# Brduino-MCU1.net
KiCad netlist of a schematic drawn in Altium Designer
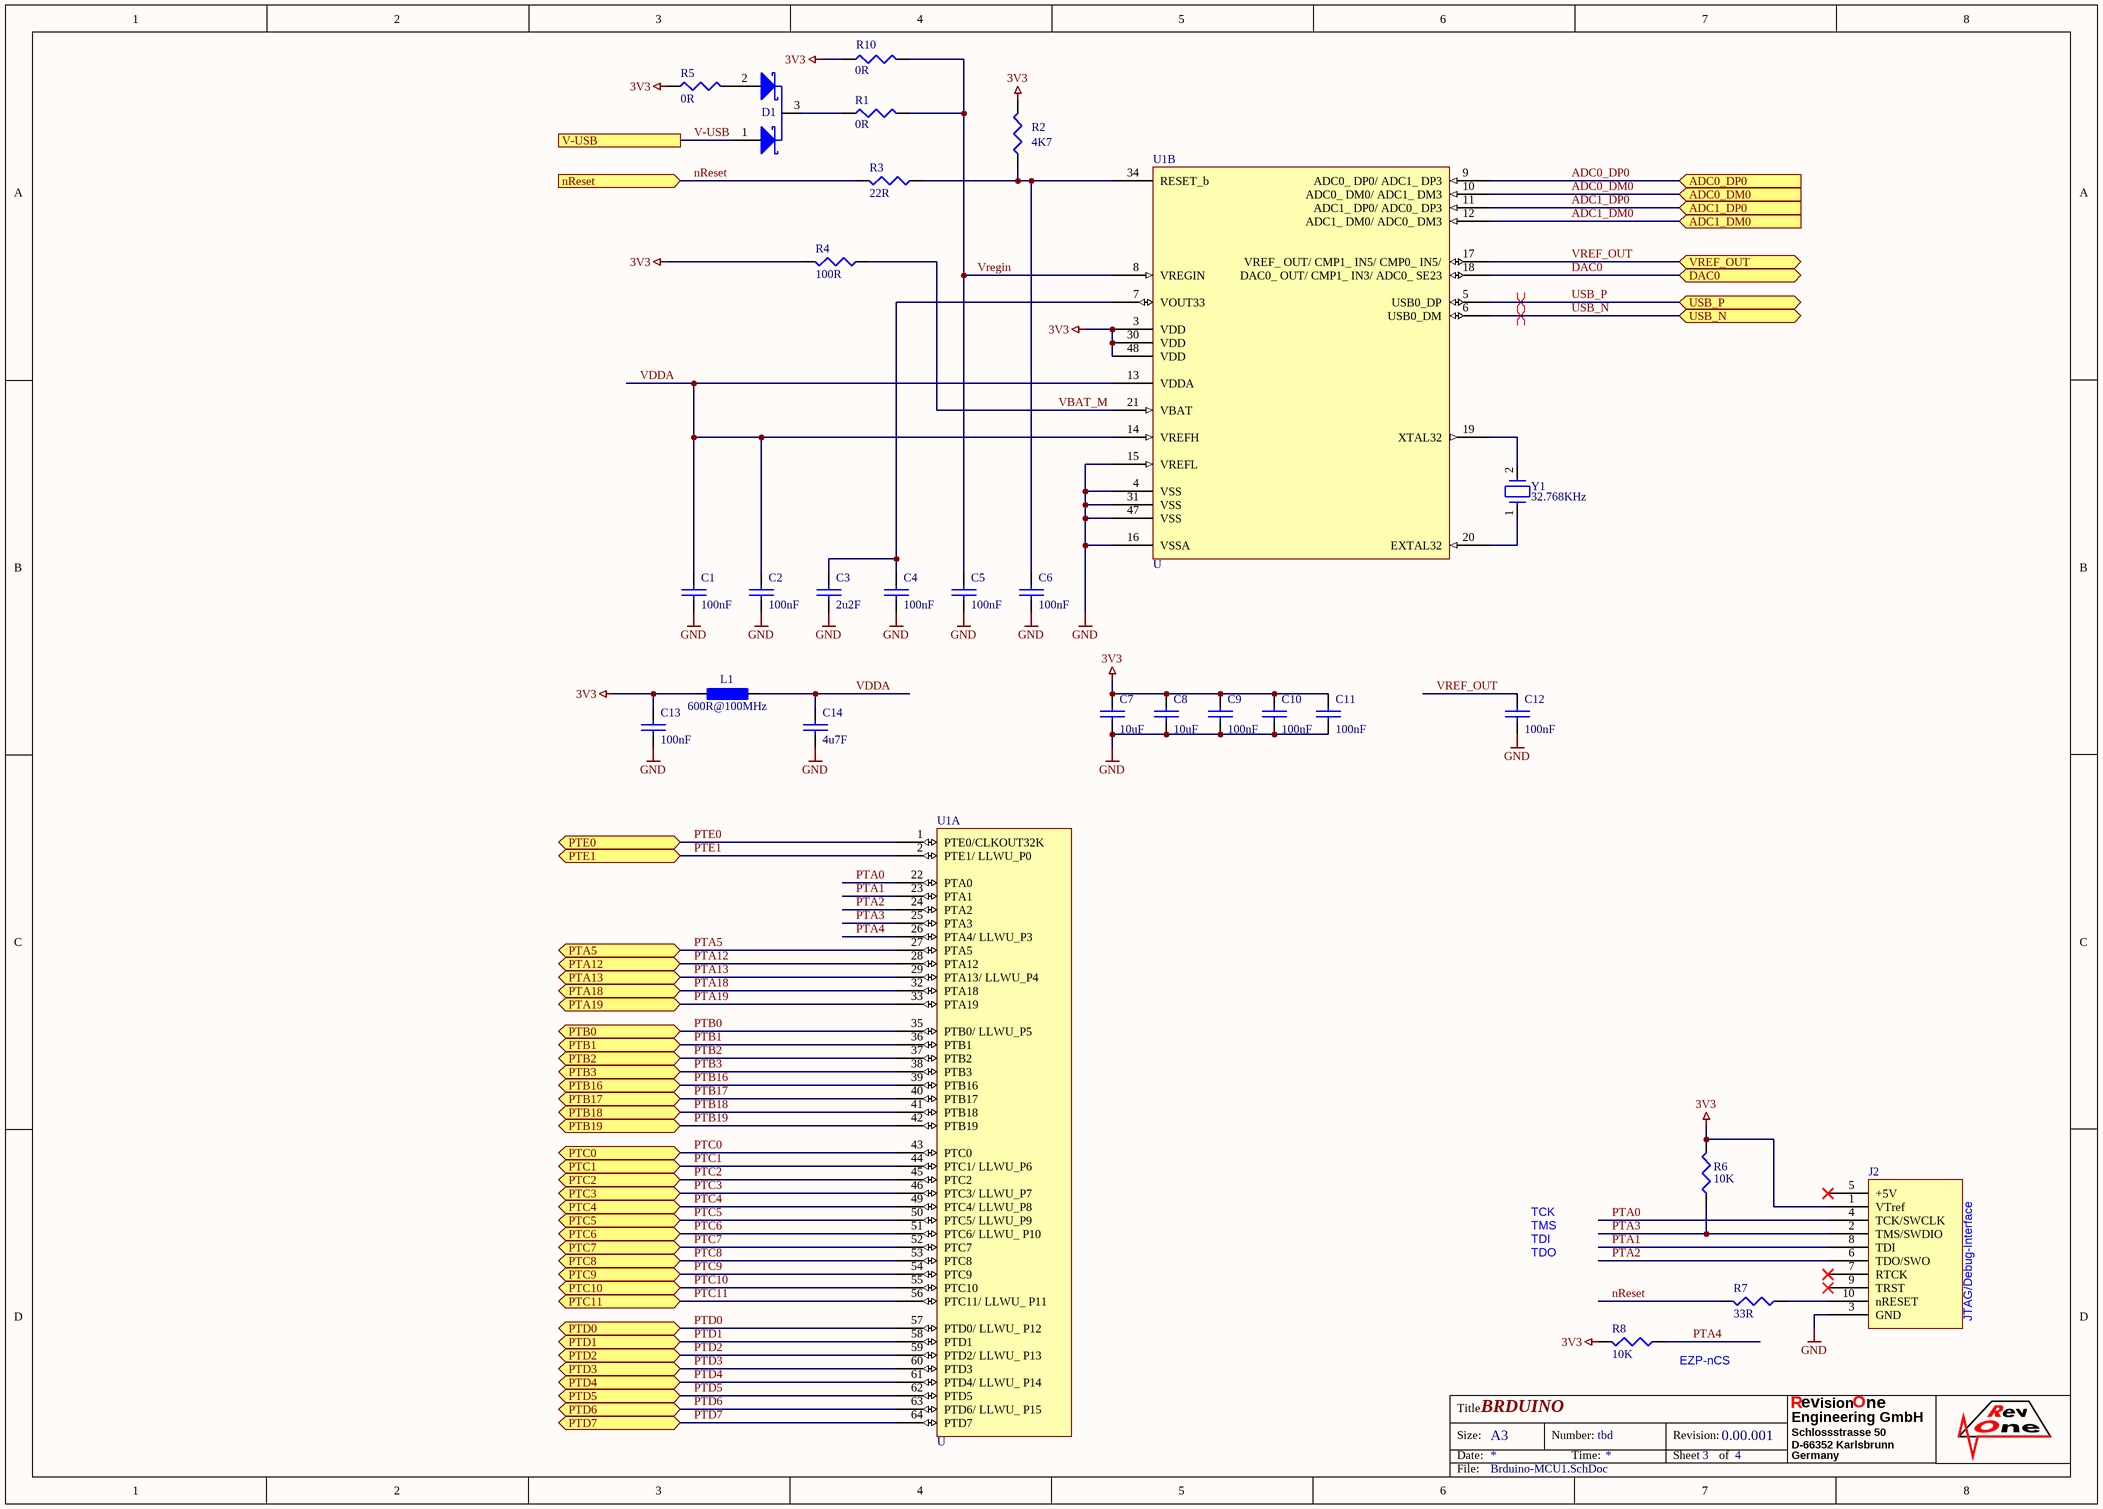
[diagram p0: Brduino-MCU1.SchDoc]

(export (version "E")
  (design (tool "Eeschema 10.0.6"))
  (components
    (comp (ref "C1")
      (value "100nF")
      (footprint "C0402")
      (description "CAP CER 0.1UF 25V X7R 0402")
      (fields (field (name "Comment") "C"))
      (libsource (lib "Brduino-Nano") (part "CAP"))
    )
    (comp (ref "C2")
      (value "100nF")
      (footprint "C0402")
      (description "CAP CER 0.1UF 25V X7R 0402")
      (fields (field (name "Comment") "C"))
      (libsource (lib "Brduino-Nano") (part "CAP"))
    )
    (comp (ref "C3")
      (value "2u2F")
      (footprint "C0603")
      (description "CAP CER 2.2UF 10V X5R 0603")
      (fields (field (name "Comment") "C"))
      (libsource (lib "Brduino-Nano") (part "CAP"))
    )
    (comp (ref "C4")
      (value "100nF")
      (footprint "C0402")
      (description "CAP CER 0.1UF 25V X7R 0402")
      (fields (field (name "Comment") "C"))
      (libsource (lib "Brduino-Nano") (part "CAP"))
    )
    (comp (ref "C5")
      (value "100nF")
      (footprint "C0402")
      (description "CAP CER 0.1UF 25V X7R 0402")
      (fields (field (name "Comment") "C"))
      (libsource (lib "Brduino-Nano") (part "CAP"))
    )
    (comp (ref "C6")
      (value "100nF")
      (footprint "C0402")
      (description "CAP CER 0.1UF 25V X7R 0402")
      (fields (field (name "Comment") "C"))
      (libsource (lib "Brduino-Nano") (part "CAP"))
    )
    (comp (ref "C7")
      (value "10uF")
      (footprint "C0805")
      (description "CAP CER 10UF 10V X7R 0805")
      (fields (field (name "Comment") "C"))
      (libsource (lib "Brduino-Nano") (part "CAP"))
    )
    (comp (ref "C8")
      (value "10uF")
      (footprint "C0805")
      (description "CAP CER 10UF 10V X7R 0805")
      (fields (field (name "Comment") "C"))
      (libsource (lib "Brduino-Nano") (part "CAP"))
    )
    (comp (ref "C9")
      (value "100nF")
      (footprint "C0402")
      (description "CAP CER 0.1UF 25V X7R 0402")
      (fields (field (name "Comment") "C"))
      (libsource (lib "Brduino-Nano") (part "CAP"))
    )
    (comp (ref "C10")
      (value "100nF")
      (footprint "C0402")
      (description "CAP CER 0.1UF 25V X7R 0402")
      (fields (field (name "Comment") "C"))
      (libsource (lib "Brduino-Nano") (part "CAP"))
    )
    (comp (ref "C11")
      (value "100nF")
      (footprint "C0402")
      (description "CAP CER 0.1UF 25V X7R 0402")
      (fields (field (name "Comment") "C"))
      (libsource (lib "Brduino-Nano") (part "CAP"))
    )
    (comp (ref "C12")
      (value "100nF")
      (footprint "C0402")
      (description "CAP CER 0.1UF 25V X7R 0402")
      (fields (field (name "Comment") "C"))
      (libsource (lib "Brduino-Nano") (part "CAP"))
    )
    (comp (ref "C13")
      (value "100nF")
      (footprint "C0402")
      (description "CAP CER 0.1UF 25V X7R 0402")
      (fields (field (name "Comment") "C"))
      (libsource (lib "Brduino-Nano") (part "CAP"))
    )
    (comp (ref "C14")
      (value "4u7F")
      (footprint "C0805")
      (description "CAP CER 4.7UF 10V X7R 0805")
      (fields (field (name "Comment") "C"))
      (libsource (lib "Brduino-Nano") (part "CAP"))
    )
    (comp (ref "D1")
      (value "D")
      (footprint "SOT23")
      (description "DIODE ARRAY SCHOTTKY 30V SOT23-3")
      (libsource (lib "Brduino-Nano") (part "DUALSDIODE-CC"))
    )
    (comp (ref "J2")
      (value "X")
      (footprint "JLINK-NEEDLE")
      (libsource (lib "Brduino-Nano") (part "JLINK-NEEDLE"))
    )
    (comp (ref "L1")
      (value "600R@100MHz")
      (footprint "L0805")
      (description "FERRITE BEAD 600 OHM 0805 1LN")
      (fields (field (name "Comment") "L"))
      (libsource (lib "Brduino-Nano") (part "FERRITE"))
    )
    (comp (ref "R1")
      (value "0R")
      (footprint "R0402")
      (description "RES SMD 0 OHM JUMPER 1/16W 0402")
      (fields (field (name "Comment") "R"))
      (libsource (lib "Brduino-Nano") (part "RES1A"))
    )
    (comp (ref "R2")
      (value "4K7")
      (footprint "R0402")
      (description "RES SMD 4.7K OHM 1% 1/16W 0402")
      (fields (field (name "Comment") "R"))
      (libsource (lib "Brduino-Nano") (part "RES1A"))
    )
    (comp (ref "R3")
      (value "22R")
      (footprint "R0402")
      (description "RES SMD 22 OHM 1% 1/16W 0402")
      (fields (field (name "Comment") "R"))
      (libsource (lib "Brduino-Nano") (part "RES1A"))
    )
    (comp (ref "R4")
      (value "100R")
      (footprint "R0402")
      (description "RES SMD 100 OHM 1% 1/16W 0402")
      (fields (field (name "Comment") "R"))
      (libsource (lib "Brduino-Nano") (part "RES1A"))
    )
    (comp (ref "R5")
      (value "0R")
      (footprint "R0402")
      (description "RES SMD 0 OHM JUMPER 1/16W 0402")
      (fields (field (name "Comment") "R"))
      (libsource (lib "Brduino-Nano") (part "RES1A"))
    )
    (comp (ref "R6")
      (value "10K")
      (footprint "R0402")
      (description "RES SMD 10K OHM 1% 1/16W 0402")
      (fields (field (name "Comment") "R"))
      (libsource (lib "Brduino-Nano") (part "RES1A"))
    )
    (comp (ref "R7")
      (value "33R")
      (footprint "R0402")
      (description "RES SMD 33 OHM 1% 1/16W 0402")
      (fields (field (name "Comment") "R"))
      (libsource (lib "Brduino-Nano") (part "RES1A"))
    )
    (comp (ref "R8")
      (value "10K")
      (footprint "R0402")
      (description "RES SMD 10K OHM 1% 1/16W 0402")
      (fields (field (name "Comment") "R"))
      (libsource (lib "Brduino-Nano") (part "RES1A"))
    )
    (comp (ref "R10")
      (value "0R")
      (footprint "R0402")
      (description "RES SMD 0 OHM JUMPER 1/16W 0402")
      (fields (field (name "Comment") "R"))
      (libsource (lib "Brduino-Nano") (part "RES1A"))
    )
    (comp (ref "U1")
      (value "U")
      (footprint "NXP-SOT1699-1")
      (description "IC MCU 32BIT 512KB FLASH 64LQFP")
      (libsource (lib "Brduino-Nano") (part "MK22FN512VLH12"))
    )
    (comp (ref "Y1")
      (value "32.768KHz")
      (footprint "CM7V-T1A")
      (description "Crystals 32.768 kHz 9.0 pF +/-20 PPM")
      (fields (field (name "Comment") "Y"))
      (libsource (lib "Brduino-Nano") (part "CM7V-T1A"))
    )
  )
  (nets
    (net (code "1") (name "/ADC0_DM0") (class "Default")
      (node (ref "U1") (pin "10") (pinfunction "ADC0__DM0/_ADC1__DM3_10") (pintype "input"))
    )
    (net (code "2") (name "/ADC0_DP0") (class "Default")
      (node (ref "U1") (pin "9") (pinfunction "ADC0__DP0/_ADC1__DP3_9") (pintype "input"))
    )
    (net (code "3") (name "/ADC1_DM0") (class "Default")
      (node (ref "U1") (pin "12") (pinfunction "ADC1__DM0/_ADC0__DM3_12") (pintype "input"))
    )
    (net (code "4") (name "/ADC1_DP0") (class "Default")
      (node (ref "U1") (pin "11") (pinfunction "ADC1__DP0/_ADC0__DP3_11") (pintype "input"))
    )
    (net (code "5") (name "/DAC0") (class "Default")
      (node (ref "U1") (pin "18") (pinfunction "DAC0__OUT/_CMP1__IN3/_ADC0__SE23_18") (pintype "bidirectional"))
    )
    (net (code "6") (name "/PTA0") (class "Default")
      (node (ref "J2") (pin "4") (pinfunction "TCK/SWCLK_4") (pintype "passive"))
      (node (ref "U1") (pin "22") (pinfunction "PTA0_22") (pintype "bidirectional"))
    )
    (net (code "7") (name "/PTA1") (class "Default")
      (node (ref "J2") (pin "8") (pinfunction "TDI_8") (pintype "passive"))
      (node (ref "U1") (pin "23") (pinfunction "PTA1_23") (pintype "bidirectional"))
    )
    (net (code "8") (name "/PTA2") (class "Default")
      (node (ref "J2") (pin "6") (pinfunction "TDO/SWO_6") (pintype "passive"))
      (node (ref "U1") (pin "24") (pinfunction "PTA2_24") (pintype "bidirectional"))
    )
    (net (code "9") (name "/PTA3") (class "Default")
      (node (ref "J2") (pin "2") (pinfunction "TMS/SWDIO_2") (pintype "passive"))
      (node (ref "R6") (pin "1") (pinfunction "1_1") (pintype "passive"))
      (node (ref "U1") (pin "25") (pinfunction "PTA3_25") (pintype "bidirectional"))
    )
    (net (code "10") (name "/PTA4") (class "Default")
      (node (ref "R8") (pin "1") (pinfunction "1_1") (pintype "passive"))
      (node (ref "U1") (pin "26") (pinfunction "PTA4/_LLWU_P3_26") (pintype "bidirectional"))
    )
    (net (code "11") (name "/PTA5") (class "Default")
      (node (ref "U1") (pin "27") (pinfunction "PTA5_27") (pintype "bidirectional"))
    )
    (net (code "12") (name "/PTA12") (class "Default")
      (node (ref "U1") (pin "28") (pinfunction "PTA12_28") (pintype "bidirectional"))
    )
    (net (code "13") (name "/PTA13") (class "Default")
      (node (ref "U1") (pin "29") (pinfunction "PTA13/_LLWU_P4_29") (pintype "bidirectional"))
    )
    (net (code "14") (name "/PTA18") (class "Default")
      (node (ref "U1") (pin "32") (pinfunction "PTA18_32") (pintype "bidirectional"))
    )
    (net (code "15") (name "/PTA19") (class "Default")
      (node (ref "U1") (pin "33") (pinfunction "PTA19_33") (pintype "bidirectional"))
    )
    (net (code "16") (name "/PTB0") (class "Default")
      (node (ref "U1") (pin "35") (pinfunction "PTB0/_LLWU_P5_35") (pintype "bidirectional"))
    )
    (net (code "17") (name "/PTB1") (class "Default")
      (node (ref "U1") (pin "36") (pinfunction "PTB1_36") (pintype "bidirectional"))
    )
    (net (code "18") (name "/PTB2") (class "Default")
      (node (ref "U1") (pin "37") (pinfunction "PTB2_37") (pintype "bidirectional"))
    )
    (net (code "19") (name "/PTB3") (class "Default")
      (node (ref "U1") (pin "38") (pinfunction "PTB3_38") (pintype "bidirectional"))
    )
    (net (code "20") (name "/PTB16") (class "Default")
      (node (ref "U1") (pin "39") (pinfunction "PTB16_39") (pintype "bidirectional"))
    )
    (net (code "21") (name "/PTB17") (class "Default")
      (node (ref "U1") (pin "40") (pinfunction "PTB17_40") (pintype "bidirectional"))
    )
    (net (code "22") (name "/PTB18") (class "Default")
      (node (ref "U1") (pin "41") (pinfunction "PTB18_41") (pintype "bidirectional"))
    )
    (net (code "23") (name "/PTB19") (class "Default")
      (node (ref "U1") (pin "42") (pinfunction "PTB19_42") (pintype "bidirectional"))
    )
    (net (code "24") (name "/PTC0") (class "Default")
      (node (ref "U1") (pin "43") (pinfunction "PTC0_43") (pintype "bidirectional"))
    )
    (net (code "25") (name "/PTC1") (class "Default")
      (node (ref "U1") (pin "44") (pinfunction "PTC1/_LLWU_P6_44") (pintype "bidirectional"))
    )
    (net (code "26") (name "/PTC2") (class "Default")
      (node (ref "U1") (pin "45") (pinfunction "PTC2_45") (pintype "bidirectional"))
    )
    (net (code "27") (name "/PTC3") (class "Default")
      (node (ref "U1") (pin "46") (pinfunction "PTC3/_LLWU_P7_46") (pintype "bidirectional"))
    )
    (net (code "28") (name "/PTC4") (class "Default")
      (node (ref "U1") (pin "49") (pinfunction "PTC4/_LLWU_P8_49") (pintype "bidirectional"))
    )
    (net (code "29") (name "/PTC5") (class "Default")
      (node (ref "U1") (pin "50") (pinfunction "PTC5/_LLWU_P9_50") (pintype "bidirectional"))
    )
    (net (code "30") (name "/PTC6") (class "Default")
      (node (ref "U1") (pin "51") (pinfunction "PTC6/_LLWU__P10_51") (pintype "bidirectional"))
    )
    (net (code "31") (name "/PTC7") (class "Default")
      (node (ref "U1") (pin "52") (pinfunction "PTC7_52") (pintype "bidirectional"))
    )
    (net (code "32") (name "/PTC8") (class "Default")
      (node (ref "U1") (pin "53") (pinfunction "PTC8_53") (pintype "bidirectional"))
    )
    (net (code "33") (name "/PTC9") (class "Default")
      (node (ref "U1") (pin "54") (pinfunction "PTC9_54") (pintype "bidirectional"))
    )
    (net (code "34") (name "/PTC10") (class "Default")
      (node (ref "U1") (pin "55") (pinfunction "PTC10_55") (pintype "bidirectional"))
    )
    (net (code "35") (name "/PTC11") (class "Default")
      (node (ref "U1") (pin "56") (pinfunction "PTC11/_LLWU__P11_56") (pintype "bidirectional"))
    )
    (net (code "36") (name "/PTD0") (class "Default")
      (node (ref "U1") (pin "57") (pinfunction "PTD0/_LLWU__P12_57") (pintype "bidirectional"))
    )
    (net (code "37") (name "/PTD1") (class "Default")
      (node (ref "U1") (pin "58") (pinfunction "PTD1_58") (pintype "bidirectional"))
    )
    (net (code "38") (name "/PTD2") (class "Default")
      (node (ref "U1") (pin "59") (pinfunction "PTD2/_LLWU__P13_59") (pintype "bidirectional"))
    )
    (net (code "39") (name "/PTD3") (class "Default")
      (node (ref "U1") (pin "60") (pinfunction "PTD3_60") (pintype "bidirectional"))
    )
    (net (code "40") (name "/PTD4") (class "Default")
      (node (ref "U1") (pin "61") (pinfunction "PTD4/_LLWU__P14_61") (pintype "bidirectional"))
    )
    (net (code "41") (name "/PTD5") (class "Default")
      (node (ref "U1") (pin "62") (pinfunction "PTD5_62") (pintype "bidirectional"))
    )
    (net (code "42") (name "/PTD6") (class "Default")
      (node (ref "U1") (pin "63") (pinfunction "PTD6/_LLWU__P15_63") (pintype "bidirectional"))
    )
    (net (code "43") (name "/PTD7") (class "Default")
      (node (ref "U1") (pin "64") (pinfunction "PTD7_64") (pintype "bidirectional"))
    )
    (net (code "44") (name "/PTE0") (class "Default")
      (node (ref "U1") (pin "1") (pinfunction "PTE0/CLKOUT32K_1") (pintype "bidirectional"))
    )
    (net (code "45") (name "/PTE1") (class "Default")
      (node (ref "U1") (pin "2") (pinfunction "PTE1/_LLWU_P0_2") (pintype "bidirectional"))
    )
    (net (code "46") (name "/USB_N") (class "Default")
      (node (ref "U1") (pin "6") (pinfunction "USB0_DM_6") (pintype "bidirectional"))
    )
    (net (code "47") (name "/USB_P") (class "Default")
      (node (ref "U1") (pin "5") (pinfunction "USB0_DP_5") (pintype "bidirectional"))
    )
    (net (code "48") (name "/V-USB") (class "Default")
      (node (ref "D1") (pin "1") (pinfunction "A_1") (pintype "passive"))
    )
    (net (code "49") (name "/VBAT_M") (class "Default")
      (node (ref "R4") (pin "1") (pinfunction "1_1") (pintype "passive"))
      (node (ref "U1") (pin "21") (pinfunction "VBAT_21") (pintype "input"))
    )
    (net (code "50") (name "/VDDA") (class "Default")
      (node (ref "C1") (pin "1") (pinfunction "1_1") (pintype "passive"))
      (node (ref "C14") (pin "2") (pinfunction "2_2") (pintype "passive"))
      (node (ref "C2") (pin "1") (pinfunction "1_1") (pintype "passive"))
      (node (ref "L1") (pin "2") (pinfunction "2_2") (pintype "passive"))
      (node (ref "U1") (pin "13") (pinfunction "VDDA_13") (pintype "power_in"))
      (node (ref "U1") (pin "14") (pinfunction "VREFH_14") (pintype "input"))
    )
    (net (code "51") (name "/VREF_OUT") (class "Default")
      (node (ref "C12") (pin "1") (pinfunction "1_1") (pintype "passive"))
      (node (ref "U1") (pin "17") (pinfunction "VREF__OUT/_CMP1__IN5/_CMP0__IN5/_17") (pintype "bidirectional"))
    )
    (net (code "52") (name "/Vregin") (class "Default")
      (node (ref "C5") (pin "1") (pinfunction "1_1") (pintype "passive"))
      (node (ref "R1") (pin "2") (pinfunction "2_2") (pintype "passive"))
      (node (ref "R10") (pin "2") (pinfunction "2_2") (pintype "passive"))
      (node (ref "U1") (pin "8") (pinfunction "VREGIN_8") (pintype "input"))
    )
    (net (code "53") (name "/nReset") (class "Default")
      (node (ref "R3") (pin "2") (pinfunction "2_2") (pintype "passive"))
      (node (ref "R7") (pin "2") (pinfunction "2_2") (pintype "passive"))
    )
    (net (code "54") (name "3V3") (class "Default")
      (node (ref "C10") (pin "1") (pinfunction "1_1") (pintype "passive"))
      (node (ref "C11") (pin "1") (pinfunction "1_1") (pintype "passive"))
      (node (ref "C13") (pin "2") (pinfunction "2_2") (pintype "passive"))
      (node (ref "C7") (pin "1") (pinfunction "1_1") (pintype "passive"))
      (node (ref "C8") (pin "1") (pinfunction "1_1") (pintype "passive"))
      (node (ref "C9") (pin "1") (pinfunction "1_1") (pintype "passive"))
      (node (ref "J2") (pin "1") (pinfunction "VTref_1") (pintype "passive"))
      (node (ref "L1") (pin "1") (pinfunction "1_1") (pintype "passive"))
      (node (ref "R10") (pin "1") (pinfunction "1_1") (pintype "passive"))
      (node (ref "R2") (pin "2") (pinfunction "2_2") (pintype "passive"))
      (node (ref "R4") (pin "2") (pinfunction "2_2") (pintype "passive"))
      (node (ref "R5") (pin "1") (pinfunction "1_1") (pintype "passive"))
      (node (ref "R6") (pin "2") (pinfunction "2_2") (pintype "passive"))
      (node (ref "R8") (pin "2") (pinfunction "2_2") (pintype "passive"))
      (node (ref "U1") (pin "3") (pinfunction "VDD_3") (pintype "power_in"))
      (node (ref "U1") (pin "30") (pinfunction "VDD_30") (pintype "power_in"))
      (node (ref "U1") (pin "48") (pinfunction "VDD_48") (pintype "power_in"))
    )
    (net (code "55") (name "GND") (class "Default")
      (node (ref "C1") (pin "2") (pinfunction "2_2") (pintype "passive"))
      (node (ref "C10") (pin "2") (pinfunction "2_2") (pintype "passive"))
      (node (ref "C11") (pin "2") (pinfunction "2_2") (pintype "passive"))
      (node (ref "C12") (pin "2") (pinfunction "2_2") (pintype "passive"))
      (node (ref "C13") (pin "1") (pinfunction "1_1") (pintype "passive"))
      (node (ref "C14") (pin "1") (pinfunction "1_1") (pintype "passive"))
      (node (ref "C2") (pin "2") (pinfunction "2_2") (pintype "passive"))
      (node (ref "C3") (pin "2") (pinfunction "2_2") (pintype "passive"))
      (node (ref "C4") (pin "2") (pinfunction "2_2") (pintype "passive"))
      (node (ref "C5") (pin "2") (pinfunction "2_2") (pintype "passive"))
      (node (ref "C6") (pin "2") (pinfunction "2_2") (pintype "passive"))
      (node (ref "C7") (pin "2") (pinfunction "2_2") (pintype "passive"))
      (node (ref "C8") (pin "2") (pinfunction "2_2") (pintype "passive"))
      (node (ref "C9") (pin "2") (pinfunction "2_2") (pintype "passive"))
      (node (ref "J2") (pin "3") (pinfunction "GND_3") (pintype "passive"))
      (node (ref "U1") (pin "15") (pinfunction "VREFL_15") (pintype "input"))
      (node (ref "U1") (pin "16") (pinfunction "VSSA_16") (pintype "power_in"))
      (node (ref "U1") (pin "31") (pinfunction "VSS_31") (pintype "power_in"))
      (node (ref "U1") (pin "4") (pinfunction "VSS_4") (pintype "power_in"))
      (node (ref "U1") (pin "47") (pinfunction "VSS_47") (pintype "power_in"))
    )
    (net (code "56") (name "Net-(D1-C)") (class "Default")
      (node (ref "D1") (pin "3") (pinfunction "C_3") (pintype "passive"))
      (node (ref "R1") (pin "1") (pinfunction "1_1") (pintype "passive"))
    )
    (net (code "57") (name "Net-(D1-K)") (class "Default")
      (node (ref "D1") (pin "2") (pinfunction "K_2") (pintype "passive"))
      (node (ref "R5") (pin "2") (pinfunction "2_2") (pintype "passive"))
    )
    (net (code "58") (name "Net-(J2-nRESET)") (class "Default")
      (node (ref "J2") (pin "10") (pinfunction "nRESET_10") (pintype "passive"))
      (node (ref "R7") (pin "1") (pinfunction "1_1") (pintype "passive"))
    )
    (net (code "59") (name "Net-(U1B-EXTAL32)") (class "Default")
      (node (ref "U1") (pin "20") (pinfunction "EXTAL32_20") (pintype "input"))
      (node (ref "Y1") (pin "1") (pinfunction "1_1") (pintype "passive"))
    )
    (net (code "60") (name "Net-(U1B-RESET_b)") (class "Default")
      (node (ref "C6") (pin "1") (pinfunction "1_1") (pintype "passive"))
      (node (ref "R2") (pin "1") (pinfunction "1_1") (pintype "passive"))
      (node (ref "R3") (pin "1") (pinfunction "1_1") (pintype "passive"))
      (node (ref "U1") (pin "34") (pinfunction "RESET_b_34") (pintype "power_in"))
    )
    (net (code "61") (name "Net-(U1B-VOUT33)") (class "Default")
      (node (ref "C3") (pin "1") (pinfunction "1_1") (pintype "passive"))
      (node (ref "C4") (pin "1") (pinfunction "1_1") (pintype "passive"))
      (node (ref "U1") (pin "7") (pinfunction "VOUT33_7") (pintype "bidirectional"))
    )
    (net (code "62") (name "Net-(U1B-XTAL32)") (class "Default")
      (node (ref "U1") (pin "19") (pinfunction "XTAL32_19") (pintype "output"))
      (node (ref "Y1") (pin "2") (pinfunction "2_2") (pintype "passive"))
    )
    (net (code "63") (name "unconnected-(J2-+5V-Pad5)") (class "Default")
      (node (ref "J2") (pin "5") (pinfunction "+5V_5") (pintype "passive+no_connect"))
    )
    (net (code "64") (name "unconnected-(J2-RTCK-Pad7)") (class "Default")
      (node (ref "J2") (pin "7") (pinfunction "RTCK_7") (pintype "passive+no_connect"))
    )
    (net (code "65") (name "unconnected-(J2-TRST-Pad9)") (class "Default")
      (node (ref "J2") (pin "9") (pinfunction "TRST_9") (pintype "passive+no_connect"))
    )
  )
)
